# Sensor_Unit_Schematic.net
KiCad netlist of a schematic drawn in EAGLE
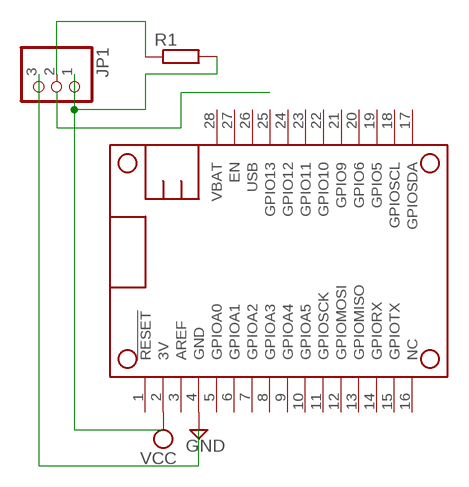
[diagram p0: schematic, sheet 1]

(export (version "E")
  (design (tool "Eeschema 10.0.6"))
  (components
    (comp (ref "JP1")
      (value "PINHD-1X3")
      (footprint "eagle-import:1X03")
      (libsource (lib "eagle-import") (part "PINHD-1X3"))
    )
    (comp (ref "MS1")
      (value "FEATHERWING_NODIM")
      (footprint "eagle-import:FEATHERWING_DIM")
      (libsource (lib "eagle-import") (part "FEATHERWING_NODIM"))
    )
    (comp (ref "R1")
      (value "R-EU_0207/10")
      (footprint "eagle-import:0207_10")
      (libsource (lib "eagle-import") (part "R-EU_0207/10"))
    )
  )
  (nets
    (net (code "1") (name "/USB") (class "Default")
      (node (ref "MS1") (pin "26") (pinfunction "USB_26") (pintype "power_in"))
    )
    (net (code "2") (name "/VBAT") (class "Default")
      (node (ref "MS1") (pin "28") (pinfunction "VBAT_28") (pintype "power_in"))
    )
    (net (code "3") (name "GND") (class "Default")
      (node (ref "MS1") (pin "4") (pinfunction "GND_4") (pintype "power_in"))
    )
    (net (code "4") (name "Net-(JP1-Pad1)") (class "Default")
      (node (ref "JP1") (pin "1") (pinfunction "1_1") (pintype "passive"))
      (node (ref "R1") (pin "2") (pinfunction "2_2") (pintype "passive"))
    )
    (net (code "5") (name "Net-(JP1-Pad2)") (class "Default")
      (node (ref "JP1") (pin "2") (pinfunction "2_2") (pintype "passive"))
      (node (ref "R1") (pin "1") (pinfunction "1_1") (pintype "passive"))
    )
    (net (code "6") (name "VCC") (class "Default")
      (node (ref "MS1") (pin "2") (pinfunction "3V_2") (pintype "power_in"))
    )
    (net (code "7") (name "unconnected-(JP1-Pad3)") (class "Default")
      (node (ref "JP1") (pin "3") (pinfunction "3_3") (pintype "passive"))
    )
    (net (code "8") (name "unconnected-(MS1-AREF-Pad3)") (class "Default")
      (node (ref "MS1") (pin "3") (pinfunction "AREF_3") (pintype "passive"))
    )
    (net (code "9") (name "unconnected-(MS1-EN-Pad27)") (class "Default")
      (node (ref "MS1") (pin "27") (pinfunction "EN_27") (pintype "passive"))
    )
    (net (code "10") (name "unconnected-(MS1-GPIO5-Pad19)") (class "Default")
      (node (ref "MS1") (pin "19") (pinfunction "GPIO5_19") (pintype "bidirectional"))
    )
    (net (code "11") (name "unconnected-(MS1-GPIO6-Pad20)") (class "Default")
      (node (ref "MS1") (pin "20") (pinfunction "GPIO6_20") (pintype "bidirectional"))
    )
    (net (code "12") (name "unconnected-(MS1-GPIO9-Pad21)") (class "Default")
      (node (ref "MS1") (pin "21") (pinfunction "GPIO9_21") (pintype "bidirectional"))
    )
    (net (code "13") (name "unconnected-(MS1-GPIO10-Pad22)") (class "Default")
      (node (ref "MS1") (pin "22") (pinfunction "GPIO10_22") (pintype "bidirectional"))
    )
    (net (code "14") (name "unconnected-(MS1-GPIO11-Pad23)") (class "Default")
      (node (ref "MS1") (pin "23") (pinfunction "GPIO11_23") (pintype "bidirectional"))
    )
    (net (code "15") (name "unconnected-(MS1-GPIO12-Pad24)") (class "Default")
      (node (ref "MS1") (pin "24") (pinfunction "GPIO12_24") (pintype "bidirectional"))
    )
    (net (code "16") (name "unconnected-(MS1-GPIO13-Pad25)") (class "Default")
      (node (ref "MS1") (pin "25") (pinfunction "GPIO13_25") (pintype "bidirectional"))
    )
    (net (code "17") (name "unconnected-(MS1-GPIOA0-Pad5)") (class "Default")
      (node (ref "MS1") (pin "5") (pinfunction "GPIOA0_5") (pintype "bidirectional"))
    )
    (net (code "18") (name "unconnected-(MS1-GPIOA1-Pad6)") (class "Default")
      (node (ref "MS1") (pin "6") (pinfunction "GPIOA1_6") (pintype "bidirectional"))
    )
    (net (code "19") (name "unconnected-(MS1-GPIOA2-Pad7)") (class "Default")
      (node (ref "MS1") (pin "7") (pinfunction "GPIOA2_7") (pintype "bidirectional"))
    )
    (net (code "20") (name "unconnected-(MS1-GPIOA3-Pad8)") (class "Default")
      (node (ref "MS1") (pin "8") (pinfunction "GPIOA3_8") (pintype "bidirectional"))
    )
    (net (code "21") (name "unconnected-(MS1-GPIOA4-Pad9)") (class "Default")
      (node (ref "MS1") (pin "9") (pinfunction "GPIOA4_9") (pintype "bidirectional"))
    )
    (net (code "22") (name "unconnected-(MS1-GPIOA5-Pad10)") (class "Default")
      (node (ref "MS1") (pin "10") (pinfunction "GPIOA5_10") (pintype "bidirectional"))
    )
    (net (code "23") (name "unconnected-(MS1-GPIOMISO-Pad13)") (class "Default")
      (node (ref "MS1") (pin "13") (pinfunction "GPIOMISO_13") (pintype "bidirectional"))
    )
    (net (code "24") (name "unconnected-(MS1-GPIOMOSI-Pad12)") (class "Default")
      (node (ref "MS1") (pin "12") (pinfunction "GPIOMOSI_12") (pintype "bidirectional"))
    )
    (net (code "25") (name "unconnected-(MS1-GPIORX-Pad14)") (class "Default")
      (node (ref "MS1") (pin "14") (pinfunction "GPIORX_14") (pintype "bidirectional"))
    )
    (net (code "26") (name "unconnected-(MS1-GPIOSCK-Pad11)") (class "Default")
      (node (ref "MS1") (pin "11") (pinfunction "GPIOSCK_11") (pintype "bidirectional"))
    )
    (net (code "27") (name "unconnected-(MS1-GPIOSCL-Pad18)") (class "Default")
      (node (ref "MS1") (pin "18") (pinfunction "GPIOSCL_18") (pintype "bidirectional"))
    )
    (net (code "28") (name "unconnected-(MS1-GPIOSDA-Pad17)") (class "Default")
      (node (ref "MS1") (pin "17") (pinfunction "GPIOSDA_17") (pintype "bidirectional"))
    )
    (net (code "29") (name "unconnected-(MS1-GPIOTX-Pad15)") (class "Default")
      (node (ref "MS1") (pin "15") (pinfunction "GPIOTX_15") (pintype "bidirectional"))
    )
    (net (code "30") (name "unconnected-(MS1-NC-Pad16)") (class "Default")
      (node (ref "MS1") (pin "16") (pinfunction "NC_16") (pintype "passive"))
    )
    (net (code "31") (name "unconnected-(MS1-~{RESET}-Pad1)") (class "Default")
      (node (ref "MS1") (pin "1") (pinfunction "~{RESET}_1") (pintype "input"))
    )
  )
)
